# Roomsensor.net
KiCad netlist of a schematic drawn in EAGLE
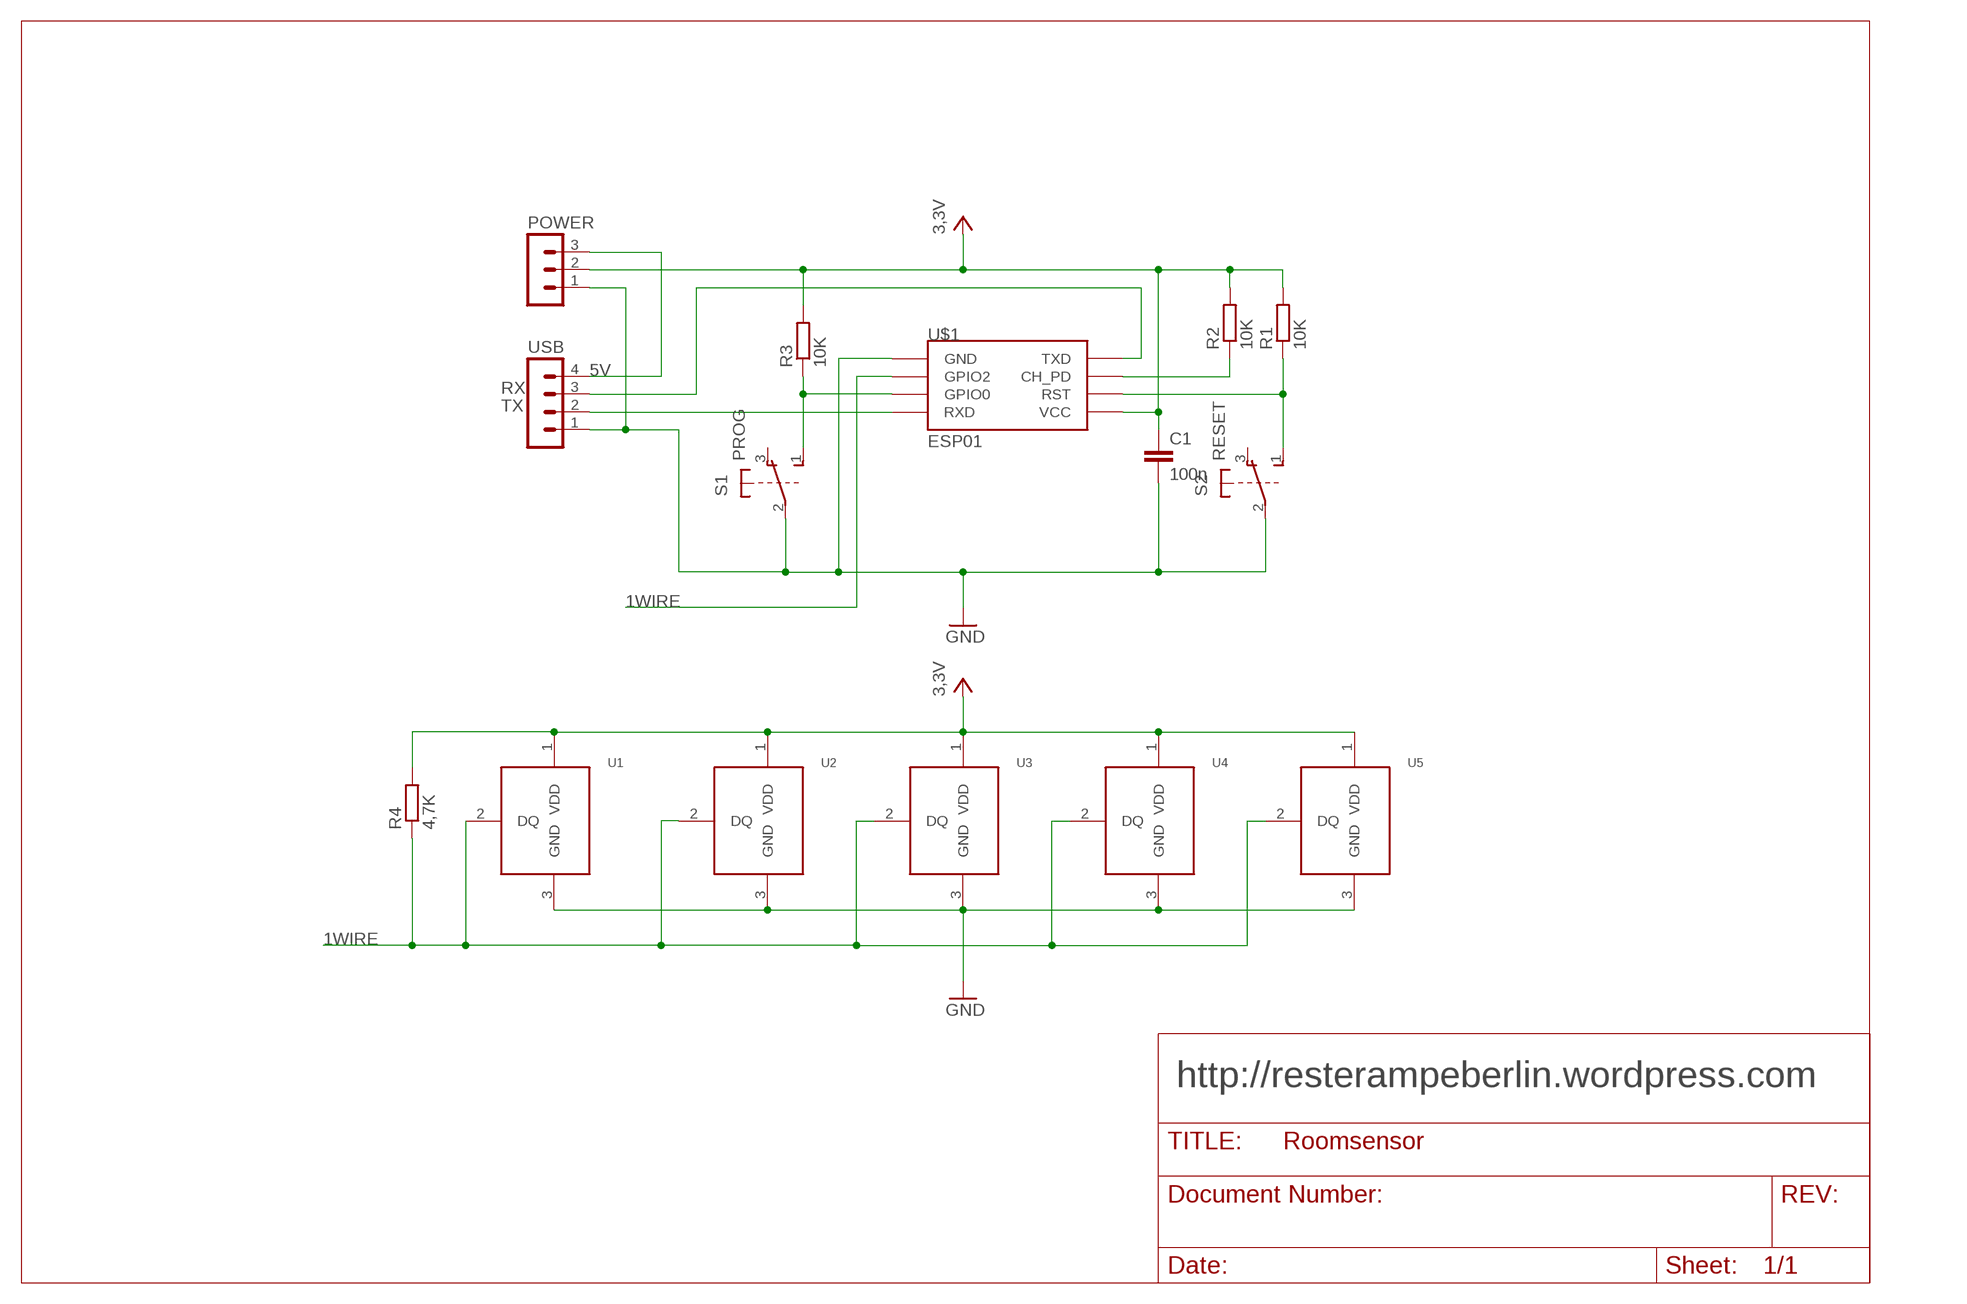
[diagram p0: schematic, sheet 1]

(export (version "E")
  (design (tool "Eeschema 10.0.6"))
  (components
    (comp (ref "C1")
      (value "100n")
      (footprint "eagle-import:C5B3")
      (libsource (lib "eagle-import") (part "C5/3"))
    )
    (comp (ref "POWER")
      (value "MA03-1")
      (footprint "eagle-import:MA03-1")
      (libsource (lib "eagle-import") (part "MA03-1"))
    )
    (comp (ref "R1")
      (value "10K")
      (footprint "eagle-import:0207_10")
      (libsource (lib "eagle-import") (part "R-EU_0207/10"))
    )
    (comp (ref "R2")
      (value "10K")
      (footprint "eagle-import:0207_10")
      (libsource (lib "eagle-import") (part "R-EU_0207/10"))
    )
    (comp (ref "R3")
      (value "10K")
      (footprint "eagle-import:0207_10")
      (libsource (lib "eagle-import") (part "R-EU_0207/10"))
    )
    (comp (ref "R4")
      (value "4,7K")
      (footprint "eagle-import:0207_10")
      (libsource (lib "eagle-import") (part "R-EU_0207/10"))
    )
    (comp (ref "S1")
      (value "PROG")
      (footprint "eagle-import:9077-2")
      (libsource (lib "eagle-import") (part "9077-2"))
    )
    (comp (ref "S2")
      (value "RESET")
      (footprint "eagle-import:9077-2")
      (libsource (lib "eagle-import") (part "9077-2"))
    )
    (comp (ref "U$1")
      (value "ESP01")
      (footprint "eagle-import:ESP01")
      (libsource (lib "eagle-import") (part "ESP01"))
    )
    (comp (ref "U1")
      (value "18S20")
      (footprint "eagle-import:TO-92")
      (libsource (lib "eagle-import") (part "18S20"))
    )
    (comp (ref "U2")
      (value "18S20")
      (footprint "eagle-import:TO-92")
      (libsource (lib "eagle-import") (part "18S20"))
    )
    (comp (ref "U3")
      (value "18S20")
      (footprint "eagle-import:TO-92")
      (libsource (lib "eagle-import") (part "18S20"))
    )
    (comp (ref "U4")
      (value "18S20")
      (footprint "eagle-import:TO-92")
      (libsource (lib "eagle-import") (part "18S20"))
    )
    (comp (ref "U5")
      (value "18S20")
      (footprint "eagle-import:TO-92")
      (libsource (lib "eagle-import") (part "18S20"))
    )
    (comp (ref "USB")
      (value "MA04-1")
      (footprint "eagle-import:MA04-1")
      (libsource (lib "eagle-import") (part "MA04-1"))
    )
  )
  (nets
    (net (code "1") (name "/1WIRE") (class "Default")
      (node (ref "R4") (pin "1") (pinfunction "1_1") (pintype "passive"))
      (node (ref "U$1") (pin "GPIO2") (pinfunction "GPIO2_GPIO2") (pintype "bidirectional"))
      (node (ref "U1") (pin "2") (pinfunction "DQ_2") (pintype "bidirectional"))
      (node (ref "U2") (pin "2") (pinfunction "DQ_2") (pintype "bidirectional"))
      (node (ref "U3") (pin "2") (pinfunction "DQ_2") (pintype "bidirectional"))
      (node (ref "U4") (pin "2") (pinfunction "DQ_2") (pintype "bidirectional"))
      (node (ref "U5") (pin "2") (pinfunction "DQ_2") (pintype "bidirectional"))
    )
    (net (code "2") (name "/5V") (class "Default")
      (node (ref "POWER") (pin "3") (pinfunction "3_3") (pintype "passive"))
      (node (ref "USB") (pin "4") (pinfunction "4_4") (pintype "passive"))
    )
    (net (code "3") (name "3,3V") (class "Default")
      (node (ref "C1") (pin "1") (pinfunction "1_1") (pintype "passive"))
      (node (ref "POWER") (pin "2") (pinfunction "2_2") (pintype "passive"))
      (node (ref "R1") (pin "2") (pinfunction "2_2") (pintype "passive"))
      (node (ref "R2") (pin "2") (pinfunction "2_2") (pintype "passive"))
      (node (ref "R3") (pin "2") (pinfunction "2_2") (pintype "passive"))
      (node (ref "R4") (pin "2") (pinfunction "2_2") (pintype "passive"))
      (node (ref "U$1") (pin "VCC") (pinfunction "VCC_VCC") (pintype "bidirectional"))
      (node (ref "U1") (pin "1") (pinfunction "VDD_1") (pintype "bidirectional"))
      (node (ref "U2") (pin "1") (pinfunction "VDD_1") (pintype "bidirectional"))
      (node (ref "U3") (pin "1") (pinfunction "VDD_1") (pintype "bidirectional"))
      (node (ref "U4") (pin "1") (pinfunction "VDD_1") (pintype "bidirectional"))
      (node (ref "U5") (pin "1") (pinfunction "VDD_1") (pintype "bidirectional"))
    )
    (net (code "4") (name "GND") (class "Default")
      (node (ref "C1") (pin "2") (pinfunction "2_2") (pintype "passive"))
      (node (ref "POWER") (pin "1") (pinfunction "1_1") (pintype "passive"))
      (node (ref "S1") (pin "2") (pinfunction "P_2") (pintype "passive"))
      (node (ref "S2") (pin "2") (pinfunction "P_2") (pintype "passive"))
      (node (ref "U$1") (pin "GND") (pinfunction "GND_GND") (pintype "bidirectional"))
      (node (ref "U1") (pin "3") (pinfunction "GND_3") (pintype "bidirectional"))
      (node (ref "U2") (pin "3") (pinfunction "GND_3") (pintype "bidirectional"))
      (node (ref "U3") (pin "3") (pinfunction "GND_3") (pintype "bidirectional"))
      (node (ref "U4") (pin "3") (pinfunction "GND_3") (pintype "bidirectional"))
      (node (ref "U5") (pin "3") (pinfunction "GND_3") (pintype "bidirectional"))
      (node (ref "USB") (pin "1") (pinfunction "1_1") (pintype "passive"))
    )
    (net (code "5") (name "Net-(R2-Pad1)") (class "Default")
      (node (ref "R2") (pin "1") (pinfunction "1_1") (pintype "passive"))
      (node (ref "U$1") (pin "CH_PD") (pinfunction "CH_PD_CH_PD") (pintype "bidirectional"))
    )
    (net (code "6") (name "Net-(S1A-S)") (class "Default")
      (node (ref "R3") (pin "1") (pinfunction "1_1") (pintype "passive"))
      (node (ref "S1") (pin "1") (pinfunction "S_1") (pintype "passive"))
      (node (ref "U$1") (pin "GPIO0") (pinfunction "GPIO0_GPIO0") (pintype "bidirectional"))
    )
    (net (code "7") (name "Net-(S2A-S)") (class "Default")
      (node (ref "R1") (pin "1") (pinfunction "1_1") (pintype "passive"))
      (node (ref "S2") (pin "1") (pinfunction "S_1") (pintype "passive"))
      (node (ref "U$1") (pin "RST") (pinfunction "RST_RST") (pintype "bidirectional"))
    )
    (net (code "8") (name "Net-(U$1-RXD)") (class "Default")
      (node (ref "U$1") (pin "RX") (pinfunction "RXD_RX") (pintype "bidirectional"))
      (node (ref "USB") (pin "2") (pinfunction "2_2") (pintype "passive"))
    )
    (net (code "9") (name "Net-(U$1-TXD)") (class "Default")
      (node (ref "U$1") (pin "TX") (pinfunction "TXD_TX") (pintype "bidirectional"))
      (node (ref "USB") (pin "3") (pinfunction "3_3") (pintype "passive"))
    )
    (net (code "10") (name "unconnected-(S1A-O-Pad3)") (class "Default")
      (node (ref "S1") (pin "3") (pinfunction "O_3") (pintype "passive"))
    )
    (net (code "11") (name "unconnected-(S2A-O-Pad3)") (class "Default")
      (node (ref "S2") (pin "3") (pinfunction "O_3") (pintype "passive"))
    )
  )
)
